# WilamowskiPI.net
KiCad netlist of a schematic drawn in EAGLE
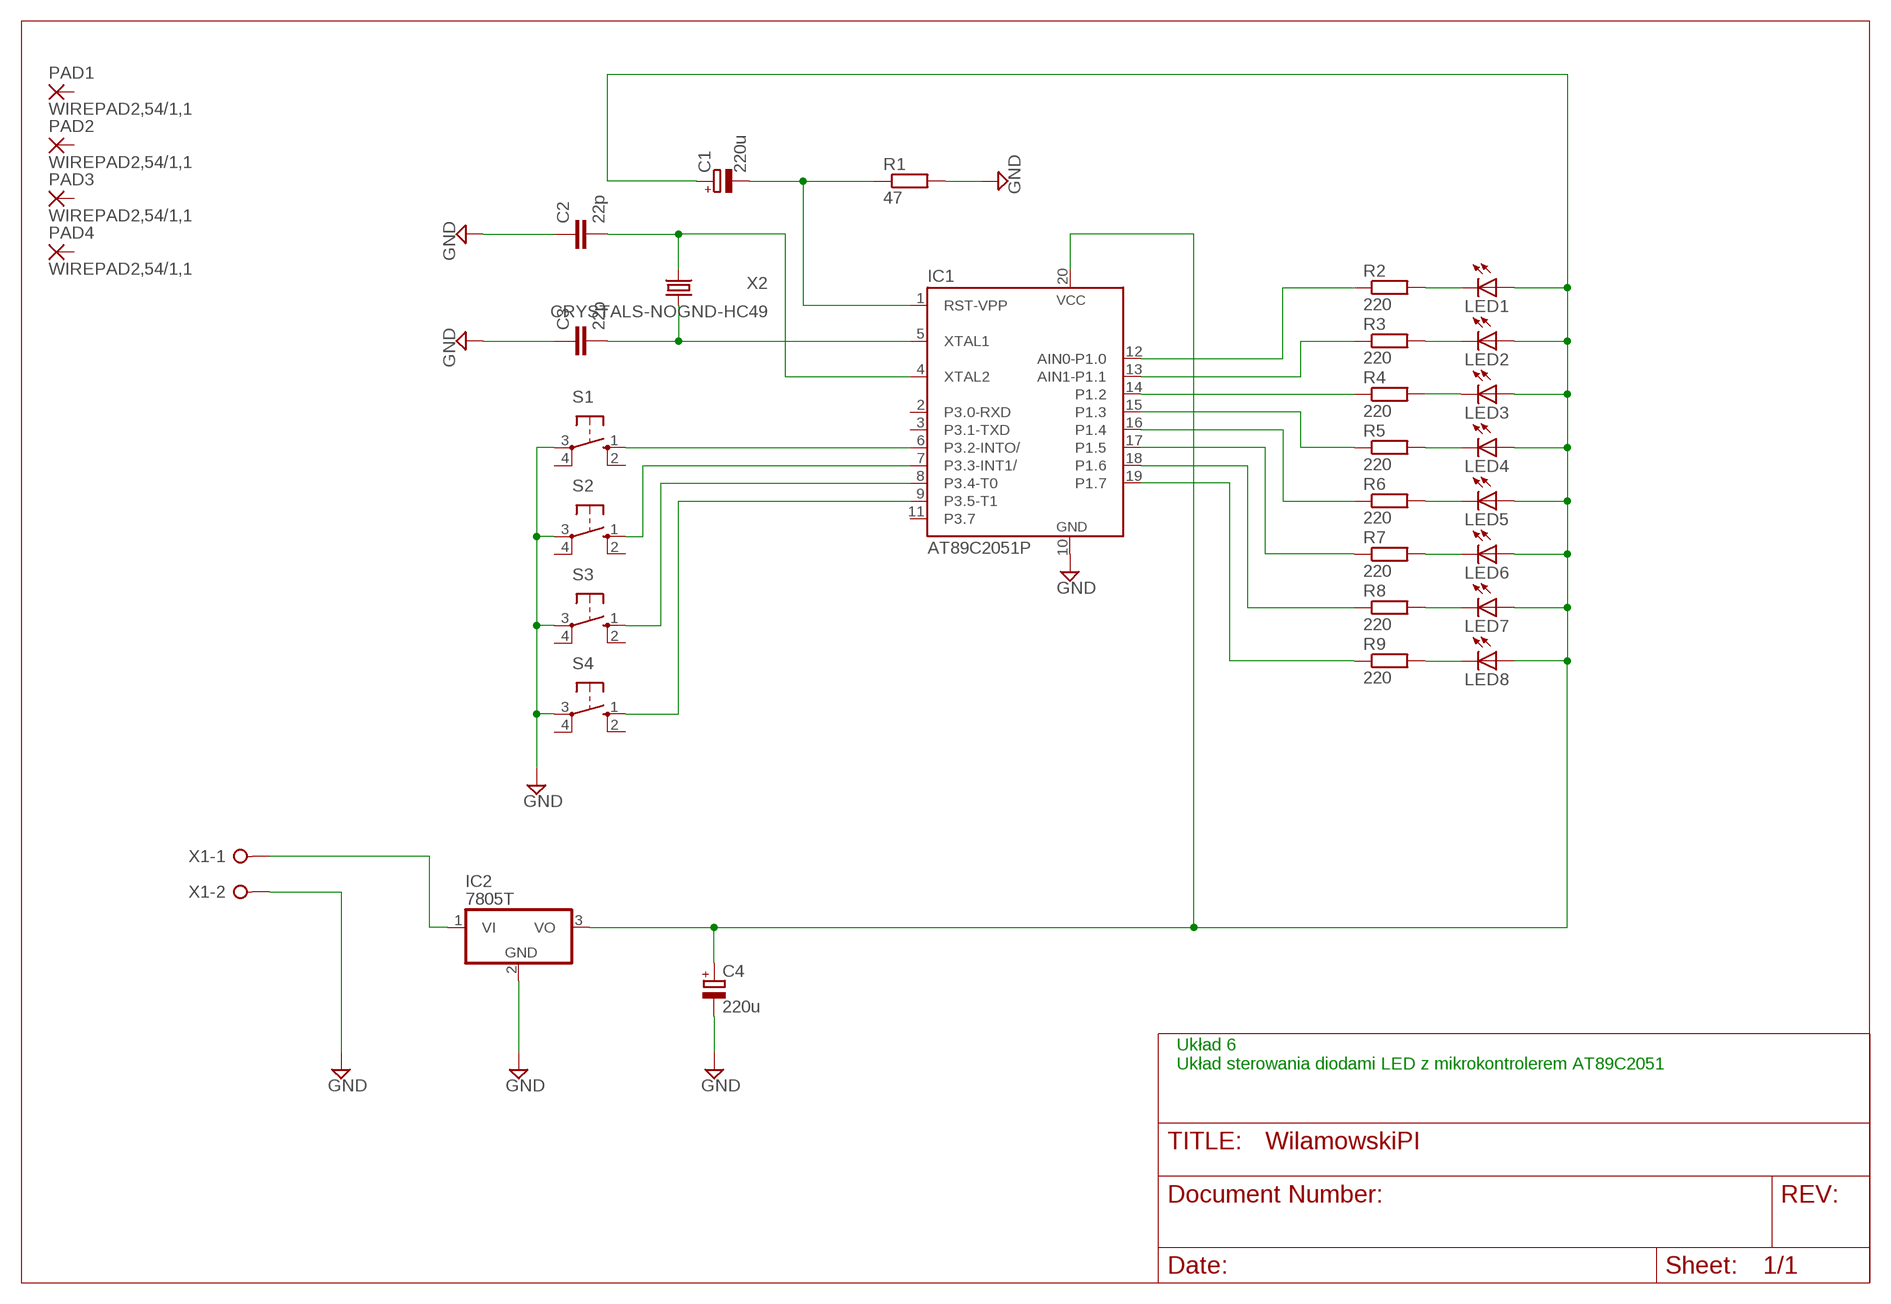
[diagram p0: schematic, sheet 1]

(export (version "E")
  (design (tool "Eeschema 10.0.6"))
  (components
    (comp (ref "C1")
      (value "220u")
      (footprint "eagle-import:E3,5-8")
      (libsource (lib "eagle-import") (part "CPOL-EUE3.5-8"))
    )
    (comp (ref "C2")
      (value "22p")
      (footprint "eagle-import:C1206")
      (libsource (lib "eagle-import") (part "C-EUC1206"))
    )
    (comp (ref "C3")
      (value "22p")
      (footprint "eagle-import:C1206")
      (libsource (lib "eagle-import") (part "C-EUC1206"))
    )
    (comp (ref "C4")
      (value "220u")
      (footprint "eagle-import:E3,5-8")
      (libsource (lib "eagle-import") (part "CPOL-EUE3.5-8"))
    )
    (comp (ref "IC1")
      (value "AT89C2051P")
      (footprint "eagle-import:DIL20")
      (fields (field (name "MPN") "AT89C2051-12PU"))
      (libsource (lib "eagle-import") (part "AT89C2051P"))
    )
    (comp (ref "IC2")
      (value "7805T")
      (footprint "eagle-import:TO220H")
      (libsource (lib "eagle-import") (part "78T05"))
    )
    (comp (ref "LED1")
      (value "LED3MM")
      (footprint "eagle-import:LED3MM")
      (libsource (lib "eagle-import") (part "LED3MM"))
    )
    (comp (ref "LED2")
      (value "LED3MM")
      (footprint "eagle-import:LED3MM")
      (libsource (lib "eagle-import") (part "LED3MM"))
    )
    (comp (ref "LED3")
      (value "LED3MM")
      (footprint "eagle-import:LED3MM")
      (libsource (lib "eagle-import") (part "LED3MM"))
    )
    (comp (ref "LED4")
      (value "LED3MM")
      (footprint "eagle-import:LED3MM")
      (libsource (lib "eagle-import") (part "LED3MM"))
    )
    (comp (ref "LED5")
      (value "LED3MM")
      (footprint "eagle-import:LED3MM")
      (libsource (lib "eagle-import") (part "LED3MM"))
    )
    (comp (ref "LED6")
      (value "LED3MM")
      (footprint "eagle-import:LED3MM")
      (libsource (lib "eagle-import") (part "LED3MM"))
    )
    (comp (ref "LED7")
      (value "LED3MM")
      (footprint "eagle-import:LED3MM")
      (libsource (lib "eagle-import") (part "LED3MM"))
    )
    (comp (ref "LED8")
      (value "LED3MM")
      (footprint "eagle-import:LED3MM")
      (libsource (lib "eagle-import") (part "LED3MM"))
    )
    (comp (ref "PAD1")
      (value "WIREPAD2,54/1,1")
      (footprint "eagle-import:2,54_1,1")
      (libsource (lib "eagle-import") (part "WIREPAD2,54/1,1"))
    )
    (comp (ref "PAD2")
      (value "WIREPAD2,54/1,1")
      (footprint "eagle-import:2,54_1,1")
      (libsource (lib "eagle-import") (part "WIREPAD2,54/1,1"))
    )
    (comp (ref "PAD3")
      (value "WIREPAD2,54/1,1")
      (footprint "eagle-import:2,54_1,1")
      (libsource (lib "eagle-import") (part "WIREPAD2,54/1,1"))
    )
    (comp (ref "PAD4")
      (value "WIREPAD2,54/1,1")
      (footprint "eagle-import:2,54_1,1")
      (libsource (lib "eagle-import") (part "WIREPAD2,54/1,1"))
    )
    (comp (ref "R1")
      (value "47")
      (footprint "eagle-import:R1206")
      (libsource (lib "eagle-import") (part "R-EU_R1206"))
    )
    (comp (ref "R2")
      (value "220")
      (footprint "eagle-import:R1206")
      (libsource (lib "eagle-import") (part "R-EU_R1206"))
    )
    (comp (ref "R3")
      (value "220")
      (footprint "eagle-import:R1206")
      (libsource (lib "eagle-import") (part "R-EU_R1206"))
    )
    (comp (ref "R4")
      (value "220")
      (footprint "eagle-import:R1206")
      (libsource (lib "eagle-import") (part "R-EU_R1206"))
    )
    (comp (ref "R5")
      (value "220")
      (footprint "eagle-import:R1206")
      (libsource (lib "eagle-import") (part "R-EU_R1206"))
    )
    (comp (ref "R6")
      (value "220")
      (footprint "eagle-import:R1206")
      (libsource (lib "eagle-import") (part "R-EU_R1206"))
    )
    (comp (ref "R7")
      (value "220")
      (footprint "eagle-import:R1206")
      (libsource (lib "eagle-import") (part "R-EU_R1206"))
    )
    (comp (ref "R8")
      (value "220")
      (footprint "eagle-import:R1206")
      (libsource (lib "eagle-import") (part "R-EU_R1206"))
    )
    (comp (ref "R9")
      (value "220")
      (footprint "eagle-import:R1206")
      (libsource (lib "eagle-import") (part "R-EU_R1206"))
    )
    (comp (ref "S1")
      (value "10-XX")
      (footprint "eagle-import:B3F-10XX")
      (fields (field (name "MPN") "B3F-1000"))
      (libsource (lib "eagle-import") (part "10-XX"))
    )
    (comp (ref "S2")
      (value "10-XX")
      (footprint "eagle-import:B3F-10XX")
      (fields (field (name "MPN") "B3F-1000"))
      (libsource (lib "eagle-import") (part "10-XX"))
    )
    (comp (ref "S3")
      (value "10-XX")
      (footprint "eagle-import:B3F-10XX")
      (fields (field (name "MPN") "B3F-1000"))
      (libsource (lib "eagle-import") (part "10-XX"))
    )
    (comp (ref "S4")
      (value "10-XX")
      (footprint "eagle-import:B3F-10XX")
      (fields (field (name "MPN") "B3F-1000"))
      (libsource (lib "eagle-import") (part "10-XX"))
    )
    (comp (ref "X1")
      (value "W237-02P")
      (footprint "eagle-import:W237-132")
      (libsource (lib "eagle-import") (part "W237-02P"))
    )
    (comp (ref "X2")
      (value "CRYSTALS-NOGND-HC49")
      (footprint "eagle-import:HC49")
      (libsource (lib "eagle-import") (part "CRYSTALS-NOGND-HC49"))
    )
  )
  (nets
    (net (code "1") (name "GND") (class "Default")
      (node (ref "C2") (pin "1") (pinfunction "1_1") (pintype "passive"))
      (node (ref "C3") (pin "1") (pinfunction "1_1") (pintype "passive"))
      (node (ref "C4") (pin "-") (pinfunction "-_-") (pintype "passive"))
      (node (ref "IC1") (pin "10") (pinfunction "GND_10") (pintype "power_in"))
      (node (ref "IC2") (pin "2") (pinfunction "GND_2") (pintype "passive"))
      (node (ref "R1") (pin "2") (pinfunction "2_2") (pintype "passive"))
      (node (ref "S1") (pin "3") (pinfunction "P_3") (pintype "passive"))
      (node (ref "S2") (pin "3") (pinfunction "P_3") (pintype "passive"))
      (node (ref "S3") (pin "3") (pinfunction "P_3") (pintype "passive"))
      (node (ref "S4") (pin "3") (pinfunction "P_3") (pintype "passive"))
      (node (ref "X1") (pin "2") (pinfunction "KL_2") (pintype "passive"))
    )
    (net (code "2") (name "Net-(IC1-AIN0-P1.0)") (class "Default")
      (node (ref "IC1") (pin "12") (pinfunction "AIN0-P1.0_12") (pintype "bidirectional"))
      (node (ref "R2") (pin "1") (pinfunction "1_1") (pintype "passive"))
    )
    (net (code "3") (name "Net-(IC1-AIN1-P1.1)") (class "Default")
      (node (ref "IC1") (pin "13") (pinfunction "AIN1-P1.1_13") (pintype "bidirectional"))
      (node (ref "R3") (pin "1") (pinfunction "1_1") (pintype "passive"))
    )
    (net (code "4") (name "Net-(IC1-P1.2)") (class "Default")
      (node (ref "IC1") (pin "14") (pinfunction "P1.2_14") (pintype "bidirectional"))
      (node (ref "R4") (pin "1") (pinfunction "1_1") (pintype "passive"))
    )
    (net (code "5") (name "Net-(IC1-P1.3)") (class "Default")
      (node (ref "IC1") (pin "15") (pinfunction "P1.3_15") (pintype "bidirectional"))
      (node (ref "R5") (pin "1") (pinfunction "1_1") (pintype "passive"))
    )
    (net (code "6") (name "Net-(IC1-P1.4)") (class "Default")
      (node (ref "IC1") (pin "16") (pinfunction "P1.4_16") (pintype "bidirectional"))
      (node (ref "R6") (pin "1") (pinfunction "1_1") (pintype "passive"))
    )
    (net (code "7") (name "Net-(IC1-P1.5)") (class "Default")
      (node (ref "IC1") (pin "17") (pinfunction "P1.5_17") (pintype "bidirectional"))
      (node (ref "R7") (pin "1") (pinfunction "1_1") (pintype "passive"))
    )
    (net (code "8") (name "Net-(IC1-P1.6)") (class "Default")
      (node (ref "IC1") (pin "18") (pinfunction "P1.6_18") (pintype "bidirectional"))
      (node (ref "R8") (pin "1") (pinfunction "1_1") (pintype "passive"))
    )
    (net (code "9") (name "Net-(IC1-P1.7)") (class "Default")
      (node (ref "IC1") (pin "19") (pinfunction "P1.7_19") (pintype "bidirectional"))
      (node (ref "R9") (pin "1") (pinfunction "1_1") (pintype "passive"))
    )
    (net (code "10") (name "Net-(IC1-P3.2-INTO{slash})") (class "Default")
      (node (ref "IC1") (pin "6") (pinfunction "P3.2-INTO/_6") (pintype "bidirectional"))
      (node (ref "S1") (pin "1") (pinfunction "S_1") (pintype "passive"))
    )
    (net (code "11") (name "Net-(IC1-P3.3-INT1{slash})") (class "Default")
      (node (ref "IC1") (pin "7") (pinfunction "P3.3-INT1/_7") (pintype "bidirectional"))
      (node (ref "S2") (pin "1") (pinfunction "S_1") (pintype "passive"))
    )
    (net (code "12") (name "Net-(IC1-P3.4-T0)") (class "Default")
      (node (ref "IC1") (pin "8") (pinfunction "P3.4-T0_8") (pintype "bidirectional"))
      (node (ref "S3") (pin "1") (pinfunction "S_1") (pintype "passive"))
    )
    (net (code "13") (name "Net-(IC1-P3.5-T1)") (class "Default")
      (node (ref "IC1") (pin "9") (pinfunction "P3.5-T1_9") (pintype "bidirectional"))
      (node (ref "S4") (pin "1") (pinfunction "S_1") (pintype "passive"))
    )
    (net (code "14") (name "Net-(IC1-RST-VPP)") (class "Default")
      (node (ref "C1") (pin "-") (pinfunction "-_-") (pintype "passive"))
      (node (ref "IC1") (pin "1") (pinfunction "RST-VPP_1") (pintype "input"))
      (node (ref "R1") (pin "1") (pinfunction "1_1") (pintype "passive"))
    )
    (net (code "15") (name "Net-(IC1-VCC)") (class "Default")
      (node (ref "C1") (pin "+") (pinfunction "+_+") (pintype "passive"))
      (node (ref "C4") (pin "+") (pinfunction "+_+") (pintype "passive"))
      (node (ref "IC1") (pin "20") (pinfunction "VCC_20") (pintype "power_in"))
      (node (ref "IC2") (pin "3") (pinfunction "VO_3") (pintype "passive"))
      (node (ref "LED1") (pin "A") (pinfunction "A_A") (pintype "passive"))
      (node (ref "LED2") (pin "A") (pinfunction "A_A") (pintype "passive"))
      (node (ref "LED3") (pin "A") (pinfunction "A_A") (pintype "passive"))
      (node (ref "LED4") (pin "A") (pinfunction "A_A") (pintype "passive"))
      (node (ref "LED5") (pin "A") (pinfunction "A_A") (pintype "passive"))
      (node (ref "LED6") (pin "A") (pinfunction "A_A") (pintype "passive"))
      (node (ref "LED7") (pin "A") (pinfunction "A_A") (pintype "passive"))
      (node (ref "LED8") (pin "A") (pinfunction "A_A") (pintype "passive"))
    )
    (net (code "16") (name "Net-(IC1-XTAL1)") (class "Default")
      (node (ref "C3") (pin "2") (pinfunction "2_2") (pintype "passive"))
      (node (ref "IC1") (pin "5") (pinfunction "XTAL1_5") (pintype "input"))
      (node (ref "X2") (pin "1") (pinfunction "1_1") (pintype "passive"))
    )
    (net (code "17") (name "Net-(IC1-XTAL2)") (class "Default")
      (node (ref "C2") (pin "2") (pinfunction "2_2") (pintype "passive"))
      (node (ref "IC1") (pin "4") (pinfunction "XTAL2_4") (pintype "output"))
      (node (ref "X2") (pin "2") (pinfunction "2_2") (pintype "passive"))
    )
    (net (code "18") (name "Net-(IC2-VI)") (class "Default")
      (node (ref "IC2") (pin "1") (pinfunction "VI_1") (pintype "input"))
      (node (ref "X1") (pin "1") (pinfunction "KL_1") (pintype "passive"))
    )
    (net (code "19") (name "Net-(LED1-C)") (class "Default")
      (node (ref "LED1") (pin "K") (pinfunction "C_K") (pintype "passive"))
      (node (ref "R2") (pin "2") (pinfunction "2_2") (pintype "passive"))
    )
    (net (code "20") (name "Net-(LED2-C)") (class "Default")
      (node (ref "LED2") (pin "K") (pinfunction "C_K") (pintype "passive"))
      (node (ref "R3") (pin "2") (pinfunction "2_2") (pintype "passive"))
    )
    (net (code "21") (name "Net-(LED3-C)") (class "Default")
      (node (ref "LED3") (pin "K") (pinfunction "C_K") (pintype "passive"))
      (node (ref "R4") (pin "2") (pinfunction "2_2") (pintype "passive"))
    )
    (net (code "22") (name "Net-(LED4-C)") (class "Default")
      (node (ref "LED4") (pin "K") (pinfunction "C_K") (pintype "passive"))
      (node (ref "R5") (pin "2") (pinfunction "2_2") (pintype "passive"))
    )
    (net (code "23") (name "Net-(LED5-C)") (class "Default")
      (node (ref "LED5") (pin "K") (pinfunction "C_K") (pintype "passive"))
      (node (ref "R6") (pin "2") (pinfunction "2_2") (pintype "passive"))
    )
    (net (code "24") (name "Net-(LED6-C)") (class "Default")
      (node (ref "LED6") (pin "K") (pinfunction "C_K") (pintype "passive"))
      (node (ref "R7") (pin "2") (pinfunction "2_2") (pintype "passive"))
    )
    (net (code "25") (name "Net-(LED7-C)") (class "Default")
      (node (ref "LED7") (pin "K") (pinfunction "C_K") (pintype "passive"))
      (node (ref "R8") (pin "2") (pinfunction "2_2") (pintype "passive"))
    )
    (net (code "26") (name "Net-(LED8-C)") (class "Default")
      (node (ref "LED8") (pin "K") (pinfunction "C_K") (pintype "passive"))
      (node (ref "R9") (pin "2") (pinfunction "2_2") (pintype "passive"))
    )
    (net (code "27") (name "unconnected-(IC1-P3.0-RXD-Pad2)") (class "Default")
      (node (ref "IC1") (pin "2") (pinfunction "P3.0-RXD_2") (pintype "bidirectional"))
    )
    (net (code "28") (name "unconnected-(IC1-P3.1-TXD-Pad3)") (class "Default")
      (node (ref "IC1") (pin "3") (pinfunction "P3.1-TXD_3") (pintype "bidirectional"))
    )
    (net (code "29") (name "unconnected-(IC1-P3.7-Pad11)") (class "Default")
      (node (ref "IC1") (pin "11") (pinfunction "P3.7_11") (pintype "bidirectional"))
    )
    (net (code "30") (name "unconnected-(PAD1-P-Pad1)") (class "Default")
      (node (ref "PAD1") (pin "1") (pinfunction "P_1") (pintype "passive"))
    )
    (net (code "31") (name "unconnected-(PAD2-P-Pad1)") (class "Default")
      (node (ref "PAD2") (pin "1") (pinfunction "P_1") (pintype "passive"))
    )
    (net (code "32") (name "unconnected-(PAD3-P-Pad1)") (class "Default")
      (node (ref "PAD3") (pin "1") (pinfunction "P_1") (pintype "passive"))
    )
    (net (code "33") (name "unconnected-(PAD4-P-Pad1)") (class "Default")
      (node (ref "PAD4") (pin "1") (pinfunction "P_1") (pintype "passive"))
    )
    (net (code "34") (name "unconnected-(S1-P1-Pad4)") (class "Default")
      (node (ref "S1") (pin "4") (pinfunction "P1_4") (pintype "passive"))
    )
    (net (code "35") (name "unconnected-(S1-S1-Pad2)") (class "Default")
      (node (ref "S1") (pin "2") (pinfunction "S1_2") (pintype "passive"))
    )
    (net (code "36") (name "unconnected-(S2-P1-Pad4)") (class "Default")
      (node (ref "S2") (pin "4") (pinfunction "P1_4") (pintype "passive"))
    )
    (net (code "37") (name "unconnected-(S2-S1-Pad2)") (class "Default")
      (node (ref "S2") (pin "2") (pinfunction "S1_2") (pintype "passive"))
    )
    (net (code "38") (name "unconnected-(S3-P1-Pad4)") (class "Default")
      (node (ref "S3") (pin "4") (pinfunction "P1_4") (pintype "passive"))
    )
    (net (code "39") (name "unconnected-(S3-S1-Pad2)") (class "Default")
      (node (ref "S3") (pin "2") (pinfunction "S1_2") (pintype "passive"))
    )
    (net (code "40") (name "unconnected-(S4-P1-Pad4)") (class "Default")
      (node (ref "S4") (pin "4") (pinfunction "P1_4") (pintype "passive"))
    )
    (net (code "41") (name "unconnected-(S4-S1-Pad2)") (class "Default")
      (node (ref "S4") (pin "2") (pinfunction "S1_2") (pintype "passive"))
    )
  )
)
